# MAIN.net
KiCad netlist of a schematic drawn in Altium Designer
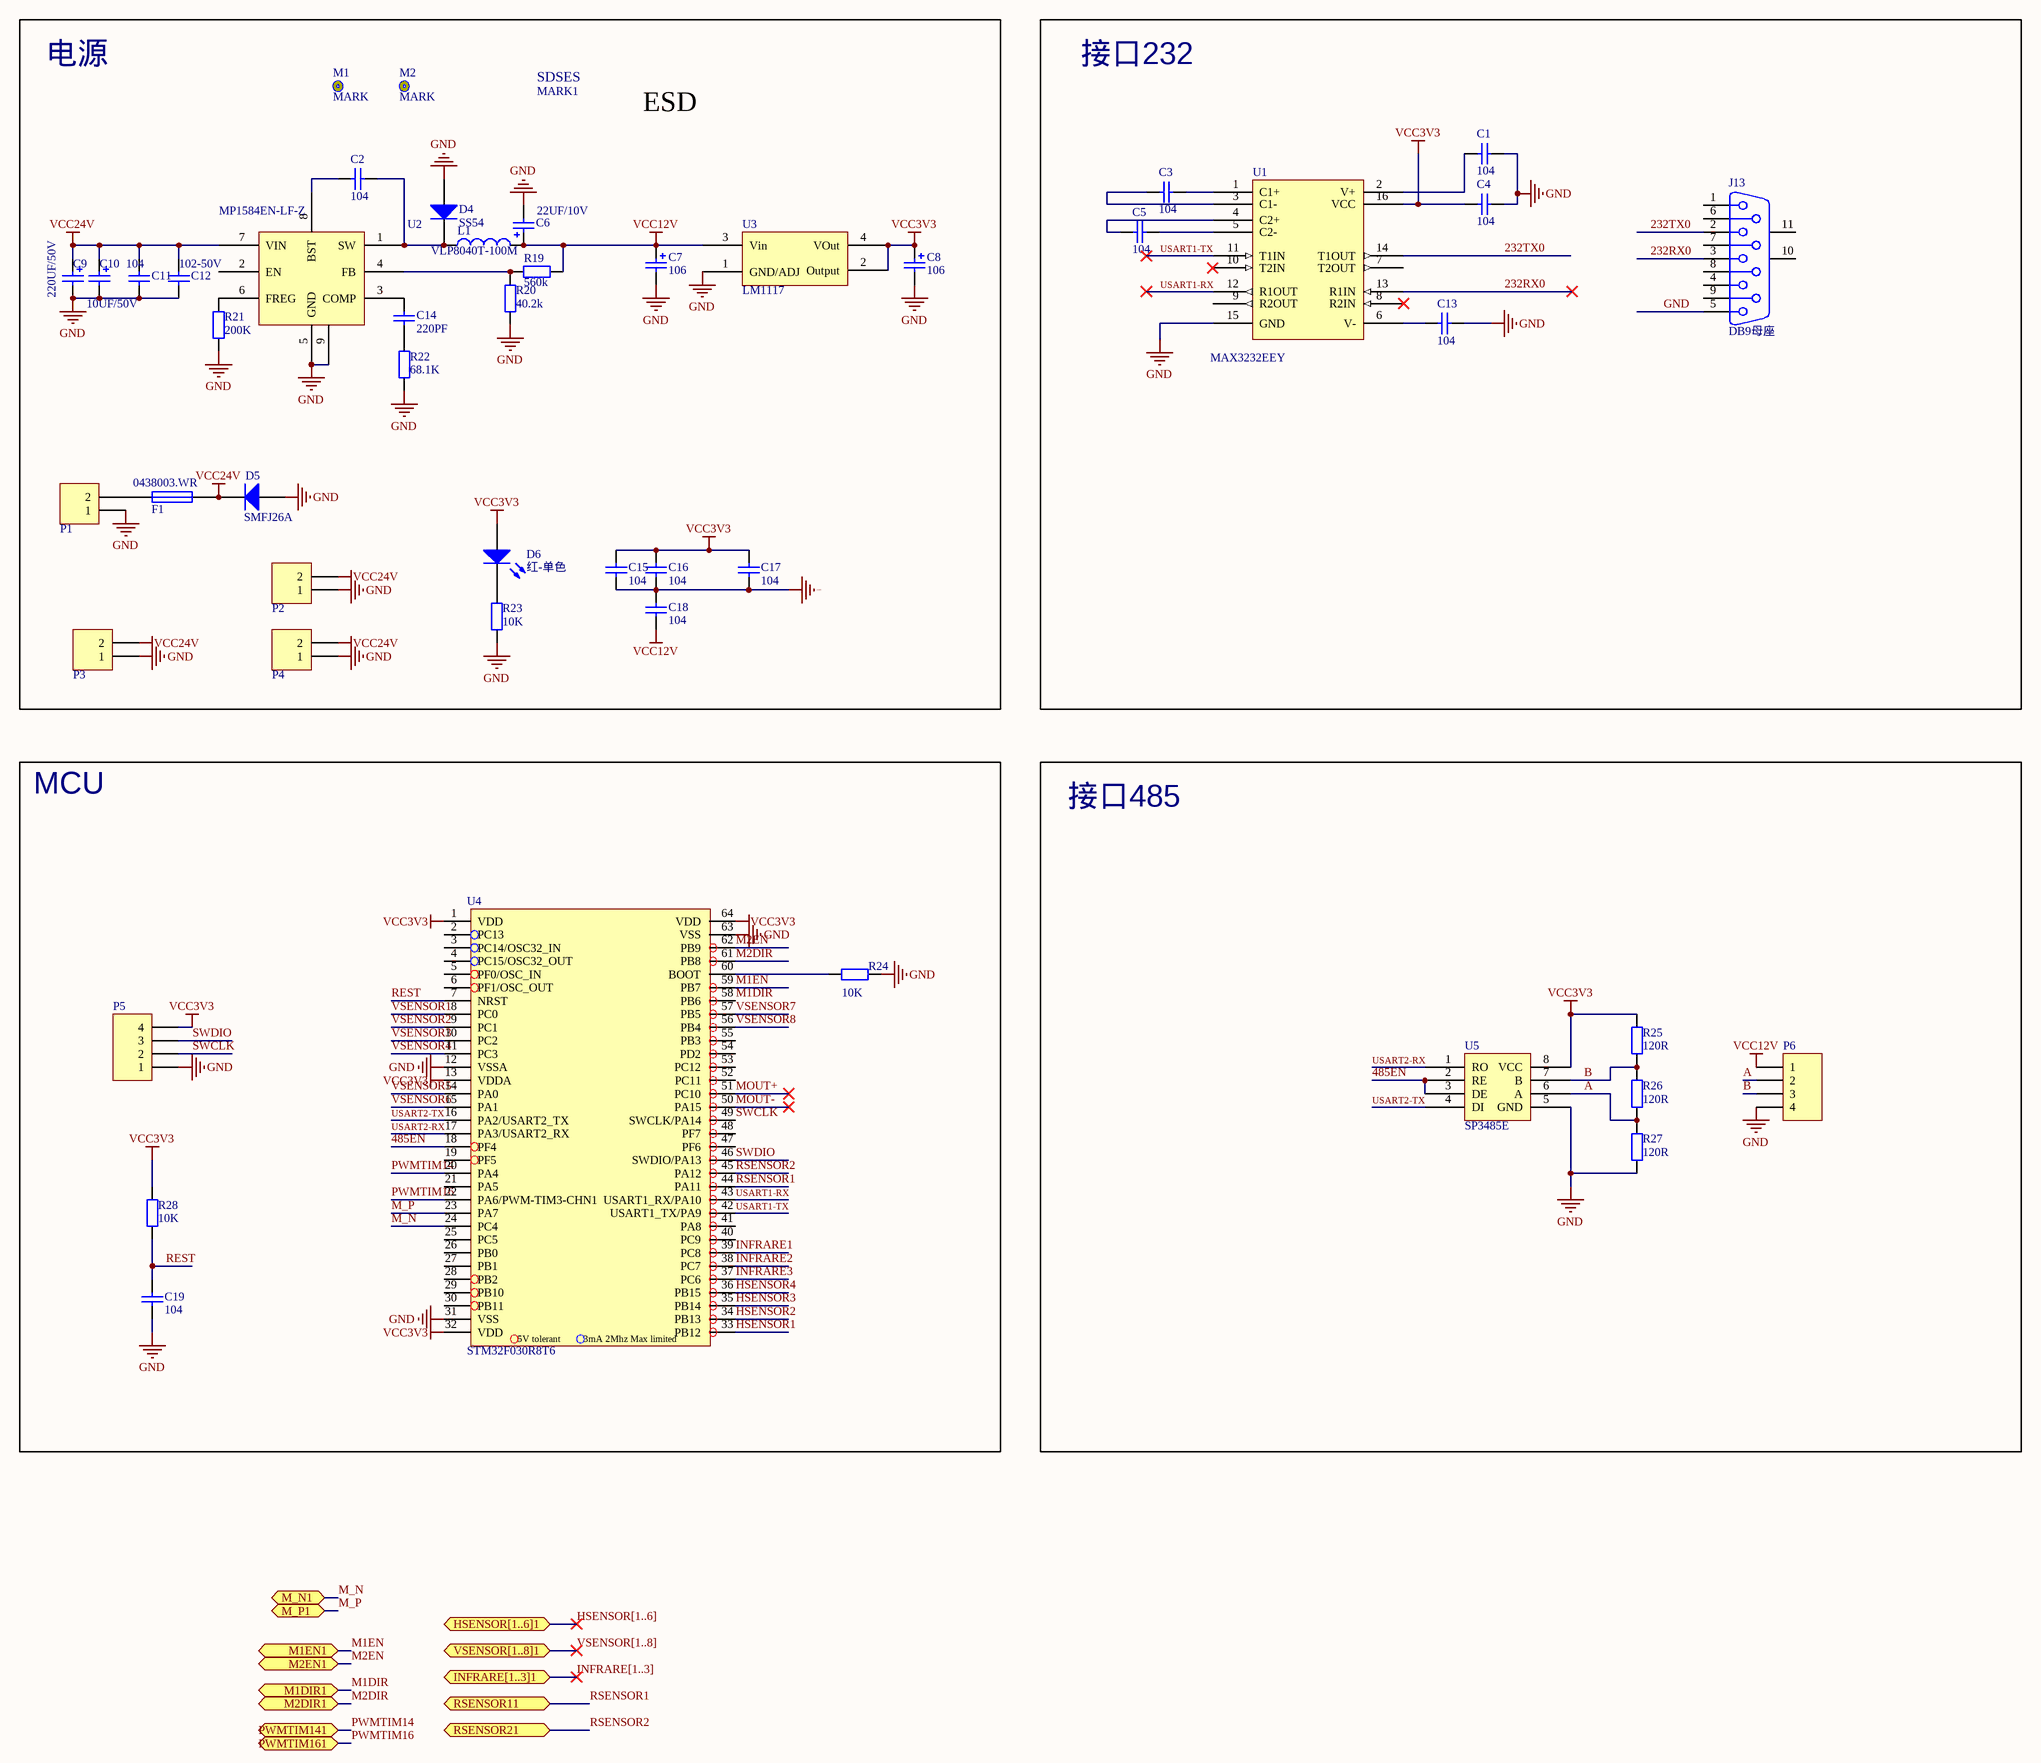
[diagram p0: MAIN.SchDoc]

(export (version "E")
  (design (tool "Eeschema 10.0.6"))
  (components
    (comp (ref "C1")
      (value "Cap_0603")
      (footprint "0603C")
      (fields (field (name "型号") "104"))
      (libsource (lib "阻容晶体管元件") (part "Cap_0603"))
    )
    (comp (ref "C2")
      (value "Cap_0603")
      (footprint "0603C")
      (fields (field (name "型号") "104"))
      (libsource (lib "阻容晶体管元件") (part "Cap_0603"))
    )
    (comp (ref "C3")
      (value "Cap_0603")
      (footprint "0603C")
      (fields (field (name "型号") "104"))
      (libsource (lib "阻容晶体管元件") (part "Cap_0603"))
    )
    (comp (ref "C4")
      (value "Cap_0603")
      (footprint "0603C")
      (fields (field (name "型号") "104"))
      (libsource (lib "阻容晶体管元件") (part "Cap_0603"))
    )
    (comp (ref "C5")
      (value "Cap_0603")
      (footprint "0603C")
      (fields (field (name "型号") "104"))
      (libsource (lib "阻容晶体管元件") (part "Cap_0603"))
    )
    (comp (ref "C6")
      (value "Cap_贴片电解电容_4*5.4")
      (footprint "CAP-D0511")
      (description "Polarized Capacitor (Radial)")
      (fields (field (name "型号") "22UF/10V"))
      (libsource (lib "阻容晶体管元件") (part "Cap_贴片电解电容_4*5.4"))
    )
    (comp (ref "C7")
      (value "Cap_钽电容B-3528")
      (footprint "0805C")
      (description "Polarized Capacitor (Radial)")
      (fields (field (name "型号") "106"))
      (libsource (lib "阻容晶体管元件") (part "Cap_钽电容B-3528"))
    )
    (comp (ref "C8")
      (value "Cap_钽电容B-3528")
      (footprint "0805C")
      (description "Polarized Capacitor (Radial)")
      (fields (field (name "型号") "106"))
      (libsource (lib "阻容晶体管元件") (part "Cap_钽电容B-3528"))
    )
    (comp (ref "C9")
      (value "Cap_贴片电解电容_6.3*5.5")
      (footprint "CAP-F0811")
      (description "Polarized Capacitor (Radial)")
      (fields (field (name "型号") "220UF/50V"))
      (libsource (lib "阻容晶体管元件") (part "Cap_贴片电解电容_6.3*5.5"))
    )
    (comp (ref "C10")
      (value "Cap_贴片电解电容_6.3*5.5")
      (footprint "CAP-D0511")
      (description "Polarized Capacitor (Radial)")
      (fields (field (name "型号") "10UF/50V"))
      (libsource (lib "阻容晶体管元件") (part "Cap_贴片电解电容_6.3*5.5"))
    )
    (comp (ref "C11")
      (value "Cap_0603")
      (footprint "0603C")
      (fields (field (name "型号") "104"))
      (libsource (lib "阻容晶体管元件") (part "Cap_0603"))
    )
    (comp (ref "C12")
      (value "Cap_0603")
      (footprint "0603C")
      (fields (field (name "型号") "102-50V"))
      (libsource (lib "阻容晶体管元件") (part "Cap_0603"))
    )
    (comp (ref "C13")
      (value "Cap_0603")
      (footprint "0603C")
      (fields (field (name "型号") "104"))
      (libsource (lib "阻容晶体管元件") (part "Cap_0603"))
    )
    (comp (ref "C14")
      (value "Cap_0603")
      (footprint "0603C")
      (fields (field (name "型号") "220PF"))
      (libsource (lib "阻容晶体管元件") (part "Cap_0603"))
    )
    (comp (ref "C15")
      (value "Cap_0603")
      (footprint "0603C")
      (fields (field (name "型号") "104"))
      (libsource (lib "阻容晶体管元件") (part "Cap_0603"))
    )
    (comp (ref "C16")
      (value "Cap_0603")
      (footprint "0603C")
      (fields (field (name "型号") "104"))
      (libsource (lib "阻容晶体管元件") (part "Cap_0603"))
    )
    (comp (ref "C17")
      (value "Cap_0603")
      (footprint "0603C")
      (fields (field (name "型号") "104"))
      (libsource (lib "阻容晶体管元件") (part "Cap_0603"))
    )
    (comp (ref "C18")
      (value "Cap_0603")
      (footprint "0603C")
      (fields (field (name "型号") "104"))
      (libsource (lib "阻容晶体管元件") (part "Cap_0603"))
    )
    (comp (ref "C19")
      (value "Cap_0603")
      (footprint "0603C")
      (fields (field (name "型号") "104"))
      (libsource (lib "阻容晶体管元件") (part "Cap_0603"))
    )
    (comp (ref "D4")
      (value "SS/SK-54/34/14")
      (footprint "DO_214AC_SMA")
      (description "Default Diode")
      (fields (field (name "型号") "SS54"))
      (libsource (lib "阻容晶体管元件") (part "SS/SK-54/34/14"))
    )
    (comp (ref "D5")
      (value "SMFJ26A")
      (footprint "SOD123-F")
      (description "Default Diode")
      (fields (field (name "型号") "SMFJ26A"))
      (libsource (lib "阻容晶体管元件") (part "Diode_DO214AC"))
    )
    (comp (ref "D6")
      (value "LED3_贴片")
      (footprint "0603_LED")
      (fields (field (name "型号") "红-单色"))
      (libsource (lib "阻容晶体管元件") (part "LED3_贴片"))
    )
    (comp (ref "F1")
      (value "FUSE")
      (footprint "1206R")
      (description "Fuse")
      (fields (field (name "型号") "0438003.WR"))
      (libsource (lib "阻容晶体管元件") (part "FUSE"))
    )
    (comp (ref "J13")
      (value "DB9母座")
      (footprint "J_DB9_M_W")
      (description "Receptacle Assembly, 9 Position, Right Angle")
      (libsource (lib "接插件") (part "D Connector 9"))
    )
    (comp (ref "L1")
      (value "L-SLF7032")
      (footprint "8040")
      (description "Inductor")
      (fields (field (name "型号") "VLP8040T-100M"))
      (libsource (lib "阻容晶体管元件") (part "L-SLF7032"))
    )
    (comp (ref "M1") (value "MARK") (footprint "MARK") (libsource (lib "集成电路") (part "MARK")))
    (comp (ref "M2") (value "MARK") (footprint "MARK") (libsource (lib "集成电路") (part "MARK")))
    (comp (ref "MARK1") (value "SDSES") (footprint "SDSES") (libsource (lib "集成电路") (part "SDSES")))
    (comp (ref "P1")
      (value "VH3.96-2-直座")
      (footprint "VH3.96-2-直座")
      (libsource (lib "接插件") (part "VH3.96-2-直座"))
    )
    (comp (ref "P2") (value "VH3.96-2P") (footprint "VH3.96-2-直座") (libsource (lib "接插件") (part "VH3.96-2P")))
    (comp (ref "P3") (value "VH3.96-2P") (footprint "VH3.96-2-直座") (libsource (lib "接插件") (part "VH3.96-2P")))
    (comp (ref "P4") (value "VH3.96-2P") (footprint "VH3.96-2-直座") (libsource (lib "接插件") (part "VH3.96-2P")))
    (comp (ref "P5")
      (value "4芯连接线焊接直针2.54")
      (footprint "SIP4_2D54F")
      (description "Header, 4-Pin")
      (libsource (lib "接插件") (part "4芯连接线带弯焊接针2.54"))
    )
    (comp (ref "P6")
      (value "XHB2.54-4PIN直座")
      (footprint "SIP4")
      (description "Header, 4-Pin")
      (libsource (lib "接插件") (part "XHB2.54-4PIN直座"))
    )
    (comp (ref "Q1")
      (value "ESD")
      (footprint "ESD")
      (description "ESD MARKER")
      (libsource (lib "阻容晶体管元件") (part "ESD"))
    )
    (comp (ref "R19")
      (value "Res_0603")
      (footprint "0603R")
      (description "Resistor")
      (fields (field (name "型号") "560k"))
      (libsource (lib "") (part "Res_0603_1"))
    )
    (comp (ref "R20")
      (value "Res_0603")
      (footprint "0603R")
      (description "Resistor")
      (fields (field (name "型号") "40.2k"))
      (libsource (lib "阻容晶体管元件") (part "Res_0603"))
    )
    (comp (ref "R21")
      (value "Res_0603")
      (footprint "0603R")
      (description "Resistor")
      (fields (field (name "型号") "200K"))
      (libsource (lib "阻容晶体管元件") (part "Res_0603"))
    )
    (comp (ref "R22")
      (value "Res_0603")
      (footprint "0603R")
      (description "Resistor")
      (fields (field (name "型号") "68.1K"))
      (libsource (lib "阻容晶体管元件") (part "Res_0603"))
    )
    (comp (ref "R23")
      (value "Res_0603")
      (footprint "0603R")
      (description "Resistor")
      (fields (field (name "型号") "10K"))
      (libsource (lib "阻容晶体管元件") (part "Res_0603"))
    )
    (comp (ref "R24")
      (value "Res_0603")
      (footprint "0603R")
      (description "Resistor")
      (fields (field (name "型号") "10K"))
      (libsource (lib "") (part "Res_0603_2"))
    )
    (comp (ref "R25")
      (value "Res_0603")
      (footprint "0603R")
      (description "Resistor")
      (fields (field (name "型号") "120R"))
      (libsource (lib "阻容晶体管元件") (part "Res_0603"))
    )
    (comp (ref "R26")
      (value "Res_0603")
      (footprint "0603R")
      (description "Resistor")
      (fields (field (name "型号") "120R"))
      (libsource (lib "阻容晶体管元件") (part "Res_0603"))
    )
    (comp (ref "R27")
      (value "Res_0603")
      (footprint "0603R")
      (description "Resistor")
      (fields (field (name "型号") "120R"))
      (libsource (lib "阻容晶体管元件") (part "Res_0603"))
    )
    (comp (ref "R28")
      (value "Res_0603")
      (footprint "0603R")
      (description "Resistor")
      (fields (field (name "型号") "10K"))
      (libsource (lib "阻容晶体管元件") (part "Res_0603"))
    )
    (comp (ref "U1")
      (value "MAX3232EEY")
      (footprint "TSSOP16")
      (description "TTL/CMOS转RS232")
      (fields (field (name "型号") "MAX3232EEY"))
      (libsource (lib "Schlib") (part "MAX3232CSE"))
    )
    (comp (ref "U2")
      (value "MP1584EN")
      (footprint "SOIC8L")
      (fields (field (name "型号") "MP1584EN-LF-Z"))
      (libsource (lib "集成电路") (part "MP1584EN"))
    )
    (comp (ref "U3") (value "LM1117") (footprint "SOT223") (libsource (lib "集成电路") (part "LM1117")))
    (comp (ref "U4")
      (value "STM32F030R8T6")
      (footprint "LQFP64")
      (fields (field (name "型号") "STM32F030R8T6"))
      (libsource (lib "集成电路") (part "STM32F030R8T6"))
    )
    (comp (ref "U5") (value "SP3485E") (footprint "SO_8") (libsource (lib "集成电路") (part "SP485E")))
  )
  (nets
    (net (code "3") (name "/232RX0") (class "Default")
      (node (ref "J13") (pin "3") (pinfunction "3_3") (pintype "passive"))
      (node (ref "U1") (pin "13") (pinfunction "R1IN_13") (pintype "input"))
    )
    (net (code "4") (name "/232TX0") (class "Default")
      (node (ref "J13") (pin "2") (pinfunction "2_2") (pintype "passive"))
      (node (ref "U1") (pin "14") (pinfunction "T1OUT_14") (pintype "output"))
    )
    (net (code "5") (name "/485EN") (class "Default")
      (node (ref "U4") (pin "18") (pinfunction "PF4_18") (pintype "passive"))
      (node (ref "U5") (pin "2") (pinfunction "RE_2") (pintype "passive"))
      (node (ref "U5") (pin "3") (pinfunction "DE_3") (pintype "passive"))
    )
    (net (code "6") (name "/A") (class "Default")
      (node (ref "P6") (pin "2") (pinfunction "2_2") (pintype "passive"))
      (node (ref "R26") (pin "1") (pinfunction "1_1") (pintype "passive"))
      (node (ref "R27") (pin "2") (pinfunction "2_2") (pintype "passive"))
      (node (ref "U5") (pin "6") (pinfunction "A_6") (pintype "passive"))
    )
    (net (code "7") (name "/B") (class "Default")
      (node (ref "P6") (pin "3") (pinfunction "3_3") (pintype "passive"))
      (node (ref "R25") (pin "1") (pinfunction "1_1") (pintype "passive"))
      (node (ref "R26") (pin "2") (pinfunction "2_2") (pintype "passive"))
      (node (ref "U5") (pin "7") (pinfunction "B_7") (pintype "passive"))
    )
    (net (code "8") (name "/HSENSOR1") (class "Default")
      (node (ref "U4") (pin "33") (pinfunction "PB12_33") (pintype "passive"))
    )
    (net (code "9") (name "/HSENSOR2") (class "Default")
      (node (ref "U4") (pin "34") (pinfunction "PB13_34") (pintype "passive"))
    )
    (net (code "10") (name "/HSENSOR3") (class "Default")
      (node (ref "U4") (pin "35") (pinfunction "PB14_35") (pintype "passive"))
    )
    (net (code "11") (name "/HSENSOR4") (class "Default")
      (node (ref "U4") (pin "36") (pinfunction "PB15_36") (pintype "passive"))
    )
    (net (code "13") (name "/INFRARE1") (class "Default")
      (node (ref "U4") (pin "39") (pinfunction "PC8_39") (pintype "passive"))
    )
    (net (code "14") (name "/INFRARE2") (class "Default")
      (node (ref "U4") (pin "38") (pinfunction "PC7_38") (pintype "passive"))
    )
    (net (code "15") (name "/INFRARE3") (class "Default")
      (node (ref "U4") (pin "37") (pinfunction "PC6_37") (pintype "passive"))
    )
    (net (code "17") (name "/M1DIR") (class "Default")
      (node (ref "U4") (pin "58") (pinfunction "PB6_58") (pintype "passive"))
    )
    (net (code "18") (name "/M1EN") (class "Default")
      (node (ref "U4") (pin "59") (pinfunction "PB7_59") (pintype "passive"))
    )
    (net (code "19") (name "/M2DIR") (class "Default")
      (node (ref "U4") (pin "61") (pinfunction "PB8_61") (pintype "passive"))
    )
    (net (code "20") (name "/M2EN") (class "Default")
      (node (ref "U4") (pin "62") (pinfunction "PB9_62") (pintype "passive"))
    )
    (net (code "21") (name "/MOUT+") (class "Default")
      (node (ref "U4") (pin "51") (pinfunction "PC10_51") (pintype "passive+no_connect"))
    )
    (net (code "22") (name "/MOUT-") (class "Default")
      (node (ref "U4") (pin "50") (pinfunction "PA15_50") (pintype "passive+no_connect"))
    )
    (net (code "23") (name "/M_N") (class "Default")
      (node (ref "U4") (pin "24") (pinfunction "PC4_24") (pintype "passive"))
    )
    (net (code "24") (name "/M_P") (class "Default")
      (node (ref "U4") (pin "23") (pinfunction "PA7_23") (pintype "passive"))
    )
    (net (code "25") (name "/PWMTIM14") (class "Default")
      (node (ref "U4") (pin "20") (pinfunction "PA4_20") (pintype "passive"))
    )
    (net (code "26") (name "/PWMTIM16") (class "Default")
      (node (ref "U4") (pin "22") (pinfunction "PA6/PWM-TIM3-CHN1_22") (pintype "passive"))
    )
    (net (code "27") (name "/REST") (class "Default")
      (node (ref "C19") (pin "2") (pinfunction "2_2") (pintype "passive"))
      (node (ref "R28") (pin "1") (pinfunction "1_1") (pintype "passive"))
      (node (ref "U4") (pin "7") (pinfunction "NRST_7") (pintype "passive"))
    )
    (net (code "28") (name "/RSENSOR1") (class "Default")
      (node (ref "U4") (pin "44") (pinfunction "PA11_44") (pintype "passive"))
    )
    (net (code "29") (name "/RSENSOR2") (class "Default")
      (node (ref "U4") (pin "45") (pinfunction "PA12_45") (pintype "passive"))
    )
    (net (code "30") (name "/SWCLK") (class "Default")
      (node (ref "P5") (pin "2") (pinfunction "2_2") (pintype "passive"))
      (node (ref "U4") (pin "49") (pinfunction "SWCLK/PA14_49") (pintype "passive"))
    )
    (net (code "31") (name "/SWDIO") (class "Default")
      (node (ref "P5") (pin "3") (pinfunction "3_3") (pintype "passive"))
      (node (ref "U4") (pin "46") (pinfunction "SWDIO/PA13_46") (pintype "passive"))
    )
    (net (code "32") (name "/USART1-RX") (class "Default")
      (node (ref "U1") (pin "12") (pinfunction "R1OUT_12") (pintype "output"))
      (node (ref "U4") (pin "43") (pinfunction "USART1_RX/PA10_43") (pintype "passive"))
    )
    (net (code "33") (name "/USART1-TX") (class "Default")
      (node (ref "U1") (pin "11") (pinfunction "T1IN_11") (pintype "input"))
      (node (ref "U4") (pin "42") (pinfunction "USART1_TX/PA9_42") (pintype "passive"))
    )
    (net (code "34") (name "/USART2-RX") (class "Default")
      (node (ref "U4") (pin "17") (pinfunction "PA3/USART2_RX_17") (pintype "passive"))
      (node (ref "U5") (pin "1") (pinfunction "RO_1") (pintype "passive"))
    )
    (net (code "35") (name "/USART2-TX") (class "Default")
      (node (ref "U4") (pin "16") (pinfunction "PA2/USART2_TX_16") (pintype "passive"))
      (node (ref "U5") (pin "4") (pinfunction "DI_4") (pintype "passive"))
    )
    (net (code "36") (name "/VSENSOR1") (class "Default")
      (node (ref "U4") (pin "8") (pinfunction "PC0_8") (pintype "passive"))
    )
    (net (code "37") (name "/VSENSOR2") (class "Default")
      (node (ref "U4") (pin "9") (pinfunction "PC1_9") (pintype "passive"))
    )
    (net (code "38") (name "/VSENSOR3") (class "Default")
      (node (ref "U4") (pin "10") (pinfunction "PC2_10") (pintype "passive"))
    )
    (net (code "39") (name "/VSENSOR4") (class "Default")
      (node (ref "U4") (pin "11") (pinfunction "PC3_11") (pintype "passive"))
    )
    (net (code "40") (name "/VSENSOR5") (class "Default")
      (node (ref "U4") (pin "14") (pinfunction "PA0_14") (pintype "passive"))
    )
    (net (code "41") (name "/VSENSOR6") (class "Default")
      (node (ref "U4") (pin "15") (pinfunction "PA1_15") (pintype "passive"))
    )
    (net (code "42") (name "/VSENSOR7") (class "Default")
      (node (ref "U4") (pin "57") (pinfunction "PB5_57") (pintype "passive"))
    )
    (net (code "43") (name "/VSENSOR8") (class "Default")
      (node (ref "U4") (pin "56") (pinfunction "PB4_56") (pintype "passive"))
    )
    (net (code "45") (name "GND") (class "Default")
      (node (ref "C1") (pin "2") (pinfunction "2_2") (pintype "passive"))
      (node (ref "C10") (pin "2") (pinfunction "2_2") (pintype "passive"))
      (node (ref "C11") (pin "1") (pinfunction "1_1") (pintype "passive"))
      (node (ref "C12") (pin "1") (pinfunction "1_1") (pintype "passive"))
      (node (ref "C13") (pin "2") (pinfunction "2_2") (pintype "passive"))
      (node (ref "C15") (pin "1") (pinfunction "1_1") (pintype "passive"))
      (node (ref "C16") (pin "2") (pinfunction "2_2") (pintype "passive"))
      (node (ref "C17") (pin "1") (pinfunction "1_1") (pintype "passive"))
      (node (ref "C18") (pin "2") (pinfunction "2_2") (pintype "passive"))
      (node (ref "C19") (pin "1") (pinfunction "1_1") (pintype "passive"))
      (node (ref "C4") (pin "2") (pinfunction "2_2") (pintype "passive"))
      (node (ref "C6") (pin "2") (pinfunction "2_2") (pintype "passive"))
      (node (ref "C7") (pin "2") (pinfunction "2_2") (pintype "passive"))
      (node (ref "C8") (pin "2") (pinfunction "2_2") (pintype "passive"))
      (node (ref "C9") (pin "2") (pinfunction "2_2") (pintype "passive"))
      (node (ref "D4") (pin "1") (pinfunction "1_1") (pintype "passive"))
      (node (ref "D5") (pin "1") (pinfunction "1_1") (pintype "passive"))
      (node (ref "J13") (pin "5") (pinfunction "5_5") (pintype "passive"))
      (node (ref "P1") (pin "1") (pinfunction "1_1") (pintype "passive"))
      (node (ref "P2") (pin "1") (pinfunction "1_1") (pintype "passive"))
      (node (ref "P3") (pin "1") (pinfunction "1_1") (pintype "passive"))
      (node (ref "P4") (pin "1") (pinfunction "1_1") (pintype "passive"))
      (node (ref "P5") (pin "1") (pinfunction "1_1") (pintype "passive"))
      (node (ref "P6") (pin "4") (pinfunction "4_4") (pintype "passive"))
      (node (ref "R20") (pin "1") (pinfunction "1_1") (pintype "passive"))
      (node (ref "R21") (pin "1") (pinfunction "1_1") (pintype "passive"))
      (node (ref "R22") (pin "1") (pinfunction "1_1") (pintype "passive"))
      (node (ref "R23") (pin "1") (pinfunction "1_1") (pintype "passive"))
      (node (ref "R24") (pin "2") (pinfunction "2_2") (pintype "passive"))
      (node (ref "R27") (pin "1") (pinfunction "1_1") (pintype "passive"))
      (node (ref "U1") (pin "15") (pinfunction "GND_15") (pintype "passive"))
      (node (ref "U2") (pin "5") (pinfunction "GND_5") (pintype "passive"))
      (node (ref "U2") (pin "9") (pinfunction "9_9") (pintype "passive"))
      (node (ref "U3") (pin "1") (pinfunction "GND/ADJ_1") (pintype "passive"))
      (node (ref "U4") (pin "12") (pinfunction "VSSA_12") (pintype "passive"))
      (node (ref "U4") (pin "31") (pinfunction "VSS_31") (pintype "passive"))
      (node (ref "U4") (pin "63") (pinfunction "VSS_63") (pintype "passive"))
      (node (ref "U5") (pin "5") (pinfunction "GND_5") (pintype "passive"))
    )
    (net (code "46") (name "Net-(C14-Pad1)") (class "Default")
      (node (ref "C14") (pin "1") (pinfunction "1_1") (pintype "passive"))
      (node (ref "R22") (pin "2") (pinfunction "2_2") (pintype "passive"))
    )
    (net (code "47") (name "Net-(D6-K)") (class "Default")
      (node (ref "D6") (pin "2") (pinfunction "K_2") (pintype "passive"))
      (node (ref "R23") (pin "2") (pinfunction "2_2") (pintype "passive"))
    )
    (net (code "48") (name "Net-(F1-Pad1)") (class "Default")
      (node (ref "F1") (pin "1") (pinfunction "1_1") (pintype "passive"))
      (node (ref "P1") (pin "2") (pinfunction "2_2") (pintype "passive"))
    )
    (net (code "49") (name "Net-(U1-C1+)") (class "Default")
      (node (ref "C3") (pin "2") (pinfunction "2_2") (pintype "passive"))
      (node (ref "U1") (pin "1") (pinfunction "C1+_1") (pintype "passive"))
    )
    (net (code "50") (name "Net-(U1-C1-)") (class "Default")
      (node (ref "C3") (pin "1") (pinfunction "1_1") (pintype "passive"))
      (node (ref "U1") (pin "3") (pinfunction "C1-_3") (pintype "passive"))
    )
    (net (code "51") (name "Net-(U1-C2+)") (class "Default")
      (node (ref "C5") (pin "1") (pinfunction "1_1") (pintype "passive"))
      (node (ref "U1") (pin "4") (pinfunction "C2+_4") (pintype "passive"))
    )
    (net (code "52") (name "Net-(U1-C2-)") (class "Default")
      (node (ref "C5") (pin "2") (pinfunction "2_2") (pintype "passive"))
      (node (ref "U1") (pin "5") (pinfunction "C2-_5") (pintype "passive"))
    )
    (net (code "53") (name "Net-(U1-V+)") (class "Default")
      (node (ref "C1") (pin "1") (pinfunction "1_1") (pintype "passive"))
      (node (ref "U1") (pin "2") (pinfunction "V+_2") (pintype "passive"))
    )
    (net (code "54") (name "Net-(U1-V-)") (class "Default")
      (node (ref "C13") (pin "1") (pinfunction "1_1") (pintype "passive"))
      (node (ref "U1") (pin "6") (pinfunction "V-_6") (pintype "passive"))
    )
    (net (code "55") (name "Net-(U2-BST)") (class "Default")
      (node (ref "C2") (pin "1") (pinfunction "1_1") (pintype "passive"))
      (node (ref "U2") (pin "8") (pinfunction "BST_8") (pintype "passive"))
    )
    (net (code "56") (name "Net-(U2-COMP)") (class "Default")
      (node (ref "C14") (pin "2") (pinfunction "2_2") (pintype "passive"))
      (node (ref "U2") (pin "3") (pinfunction "COMP_3") (pintype "passive"))
    )
    (net (code "57") (name "Net-(U2-FB)") (class "Default")
      (node (ref "R19") (pin "2") (pinfunction "2_2") (pintype "passive"))
      (node (ref "R20") (pin "2") (pinfunction "2_2") (pintype "passive"))
      (node (ref "U2") (pin "4") (pinfunction "FB_4") (pintype "passive"))
    )
    (net (code "58") (name "Net-(U2-FREG)") (class "Default")
      (node (ref "R21") (pin "2") (pinfunction "2_2") (pintype "passive"))
      (node (ref "U2") (pin "6") (pinfunction "FREG_6") (pintype "passive"))
    )
    (net (code "59") (name "Net-(U2-SW)") (class "Default")
      (node (ref "C2") (pin "2") (pinfunction "2_2") (pintype "passive"))
      (node (ref "D4") (pin "2") (pinfunction "2_2") (pintype "passive"))
      (node (ref "L1") (pin "1") (pinfunction "1_1") (pintype "passive"))
      (node (ref "U2") (pin "1") (pinfunction "SW_1") (pintype "passive"))
    )
    (net (code "60") (name "Net-(U4-BOOT)") (class "Default")
      (node (ref "R24") (pin "1") (pinfunction "1_1") (pintype "passive"))
      (node (ref "U4") (pin "60") (pinfunction "BOOT_60") (pintype "passive"))
    )
    (net (code "61") (name "VCC3V3") (class "Default")
      (node (ref "C15") (pin "2") (pinfunction "2_2") (pintype "passive"))
      (node (ref "C16") (pin "1") (pinfunction "1_1") (pintype "passive"))
      (node (ref "C17") (pin "2") (pinfunction "2_2") (pintype "passive"))
      (node (ref "C4") (pin "1") (pinfunction "1_1") (pintype "passive"))
      (node (ref "C8") (pin "1") (pinfunction "1_1") (pintype "passive"))
      (node (ref "D6") (pin "1") (pinfunction "A_1") (pintype "passive"))
      (node (ref "P5") (pin "4") (pinfunction "4_4") (pintype "passive"))
      (node (ref "R25") (pin "2") (pinfunction "2_2") (pintype "passive"))
      (node (ref "R28") (pin "2") (pinfunction "2_2") (pintype "passive"))
      (node (ref "U1") (pin "16") (pinfunction "VCC_16") (pintype "passive"))
      (node (ref "U3") (pin "2") (pinfunction "Output_2") (pintype "passive"))
      (node (ref "U3") (pin "4") (pinfunction "VOut_4") (pintype "passive"))
      (node (ref "U4") (pin "1") (pinfunction "VDD_1") (pintype "passive"))
      (node (ref "U4") (pin "13") (pinfunction "VDDA_13") (pintype "passive"))
      (node (ref "U4") (pin "32") (pinfunction "VDD_32") (pintype "passive"))
      (node (ref "U4") (pin "64") (pinfunction "VDD_64") (pintype "passive"))
      (node (ref "U5") (pin "8") (pinfunction "VCC_8") (pintype "passive"))
    )
    (net (code "62") (name "VCC12V") (class "Default")
      (node (ref "C18") (pin "1") (pinfunction "1_1") (pintype "passive"))
      (node (ref "C6") (pin "1") (pinfunction "1_1") (pintype "passive"))
      (node (ref "C7") (pin "1") (pinfunction "1_1") (pintype "passive"))
      (node (ref "L1") (pin "2") (pinfunction "2_2") (pintype "passive"))
      (node (ref "P6") (pin "1") (pinfunction "1_1") (pintype "passive"))
      (node (ref "R19") (pin "1") (pinfunction "1_1") (pintype "passive"))
      (node (ref "U3") (pin "3") (pinfunction "Vin_3") (pintype "passive"))
    )
    (net (code "63") (name "VCC24V") (class "Default")
      (node (ref "C10") (pin "1") (pinfunction "1_1") (pintype "passive"))
      (node (ref "C11") (pin "2") (pinfunction "2_2") (pintype "passive"))
      (node (ref "C12") (pin "2") (pinfunction "2_2") (pintype "passive"))
      (node (ref "C9") (pin "1") (pinfunction "1_1") (pintype "passive"))
      (node (ref "D5") (pin "2") (pinfunction "2_2") (pintype "passive"))
      (node (ref "F1") (pin "2") (pinfunction "2_2") (pintype "passive"))
      (node (ref "P2") (pin "2") (pinfunction "2_2") (pintype "passive"))
      (node (ref "P3") (pin "2") (pinfunction "2_2") (pintype "passive"))
      (node (ref "P4") (pin "2") (pinfunction "2_2") (pintype "passive"))
      (node (ref "U2") (pin "7") (pinfunction "VIN_7") (pintype "passive"))
    )
    (net (code "64") (name "unconnected-(J13-MH1-Pad10)") (class "Default")
      (node (ref "J13") (pin "10") (pinfunction "MH1_10") (pintype "passive"))
    )
    (net (code "65") (name "unconnected-(J13-MH2-Pad11)") (class "Default")
      (node (ref "J13") (pin "11") (pinfunction "MH2_11") (pintype "passive"))
    )
    (net (code "66") (name "unconnected-(J13-Pad1)") (class "Default")
      (node (ref "J13") (pin "1") (pinfunction "1_1") (pintype "passive"))
    )
    (net (code "67") (name "unconnected-(J13-Pad4)") (class "Default")
      (node (ref "J13") (pin "4") (pinfunction "4_4") (pintype "passive"))
    )
    (net (code "68") (name "unconnected-(J13-Pad6)") (class "Default")
      (node (ref "J13") (pin "6") (pinfunction "6_6") (pintype "passive"))
    )
    (net (code "69") (name "unconnected-(J13-Pad7)") (class "Default")
      (node (ref "J13") (pin "7") (pinfunction "7_7") (pintype "passive"))
    )
    (net (code "70") (name "unconnected-(J13-Pad8)") (class "Default")
      (node (ref "J13") (pin "8") (pinfunction "8_8") (pintype "passive"))
    )
    (net (code "71") (name "unconnected-(J13-Pad9)") (class "Default")
      (node (ref "J13") (pin "9") (pinfunction "9_9") (pintype "passive"))
    )
    (net (code "72") (name "unconnected-(U1-R2IN-Pad8)") (class "Default")
      (node (ref "U1") (pin "8") (pinfunction "R2IN_8") (pintype "input+no_connect"))
    )
    (net (code "73") (name "unconnected-(U1-R2OUT-Pad9)") (class "Default")
      (node (ref "U1") (pin "9") (pinfunction "R2OUT_9") (pintype "output"))
    )
    (net (code "74") (name "unconnected-(U1-T2IN-Pad10)") (class "Default")
      (node (ref "U1") (pin "10") (pinfunction "T2IN_10") (pintype "input+no_connect"))
    )
    (net (code "75") (name "unconnected-(U1-T2OUT-Pad7)") (class "Default")
      (node (ref "U1") (pin "7") (pinfunction "T2OUT_7") (pintype "output"))
    )
    (net (code "76") (name "unconnected-(U2-EN-Pad2)") (class "Default")
      (node (ref "U2") (pin "2") (pinfunction "EN_2") (pintype "passive"))
    )
    (net (code "77") (name "unconnected-(U4-PA5-Pad21)") (class "Default")
      (node (ref "U4") (pin "21") (pinfunction "PA5_21") (pintype "passive"))
    )
    (net (code "78") (name "unconnected-(U4-PA8-Pad41)") (class "Default")
      (node (ref "U4") (pin "41") (pinfunction "PA8_41") (pintype "passive"))
    )
    (net (code "79") (name "unconnected-(U4-PB0-Pad26)") (class "Default")
      (node (ref "U4") (pin "26") (pinfunction "PB0_26") (pintype "passive"))
    )
    (net (code "80") (name "unconnected-(U4-PB1-Pad27)") (class "Default")
      (node (ref "U4") (pin "27") (pinfunction "PB1_27") (pintype "passive"))
    )
    (net (code "81") (name "unconnected-(U4-PB2-Pad28)") (class "Default")
      (node (ref "U4") (pin "28") (pinfunction "PB2_28") (pintype "passive"))
    )
    (net (code "82") (name "unconnected-(U4-PB3-Pad55)") (class "Default")
      (node (ref "U4") (pin "55") (pinfunction "PB3_55") (pintype "passive"))
    )
    (net (code "83") (name "unconnected-(U4-PB10-Pad29)") (class "Default")
      (node (ref "U4") (pin "29") (pinfunction "PB10_29") (pintype "passive"))
    )
    (net (code "84") (name "unconnected-(U4-PB11-Pad30)") (class "Default")
      (node (ref "U4") (pin "30") (pinfunction "PB11_30") (pintype "passive"))
    )
    (net (code "85") (name "unconnected-(U4-PC5-Pad25)") (class "Default")
      (node (ref "U4") (pin "25") (pinfunction "PC5_25") (pintype "passive"))
    )
    (net (code "86") (name "unconnected-(U4-PC9-Pad40)") (class "Default")
      (node (ref "U4") (pin "40") (pinfunction "PC9_40") (pintype "passive"))
    )
    (net (code "87") (name "unconnected-(U4-PC11-Pad52)") (class "Default")
      (node (ref "U4") (pin "52") (pinfunction "PC11_52") (pintype "passive"))
    )
    (net (code "88") (name "unconnected-(U4-PC12-Pad53)") (class "Default")
      (node (ref "U4") (pin "53") (pinfunction "PC12_53") (pintype "passive"))
    )
    (net (code "89") (name "unconnected-(U4-PC13-Pad2)") (class "Default")
      (node (ref "U4") (pin "2") (pinfunction "PC13_2") (pintype "passive"))
    )
    (net (code "90") (name "unconnected-(U4-PC14{slash}OSC32_IN-Pad3)") (class "Default")
      (node (ref "U4") (pin "3") (pinfunction "PC14/OSC32_IN_3") (pintype "passive"))
    )
    (net (code "91") (name "unconnected-(U4-PC15{slash}OSC32_OUT-Pad4)") (class "Default")
      (node (ref "U4") (pin "4") (pinfunction "PC15/OSC32_OUT_4") (pintype "passive"))
    )
    (net (code "92") (name "unconnected-(U4-PD2-Pad54)") (class "Default")
      (node (ref "U4") (pin "54") (pinfunction "PD2_54") (pintype "passive"))
    )
    (net (code "93") (name "unconnected-(U4-PF0{slash}OSC_IN-Pad5)") (class "Default")
      (node (ref "U4") (pin "5") (pinfunction "PF0/OSC_IN_5") (pintype "passive"))
    )
    (net (code "94") (name "unconnected-(U4-PF1{slash}OSC_OUT-Pad6)") (class "Default")
      (node (ref "U4") (pin "6") (pinfunction "PF1/OSC_OUT_6") (pintype "passive"))
    )
    (net (code "95") (name "unconnected-(U4-PF5-Pad19)") (class "Default")
      (node (ref "U4") (pin "19") (pinfunction "PF5_19") (pintype "passive"))
    )
    (net (code "96") (name "unconnected-(U4-PF6-Pad47)") (class "Default")
      (node (ref "U4") (pin "47") (pinfunction "PF6_47") (pintype "passive"))
    )
    (net (code "97") (name "unconnected-(U4-PF7-Pad48)") (class "Default")
      (node (ref "U4") (pin "48") (pinfunction "PF7_48") (pintype "passive"))
    )
  )
)
